# 4xthermocoupleshield.net
KiCad netlist of a schematic drawn in EAGLE
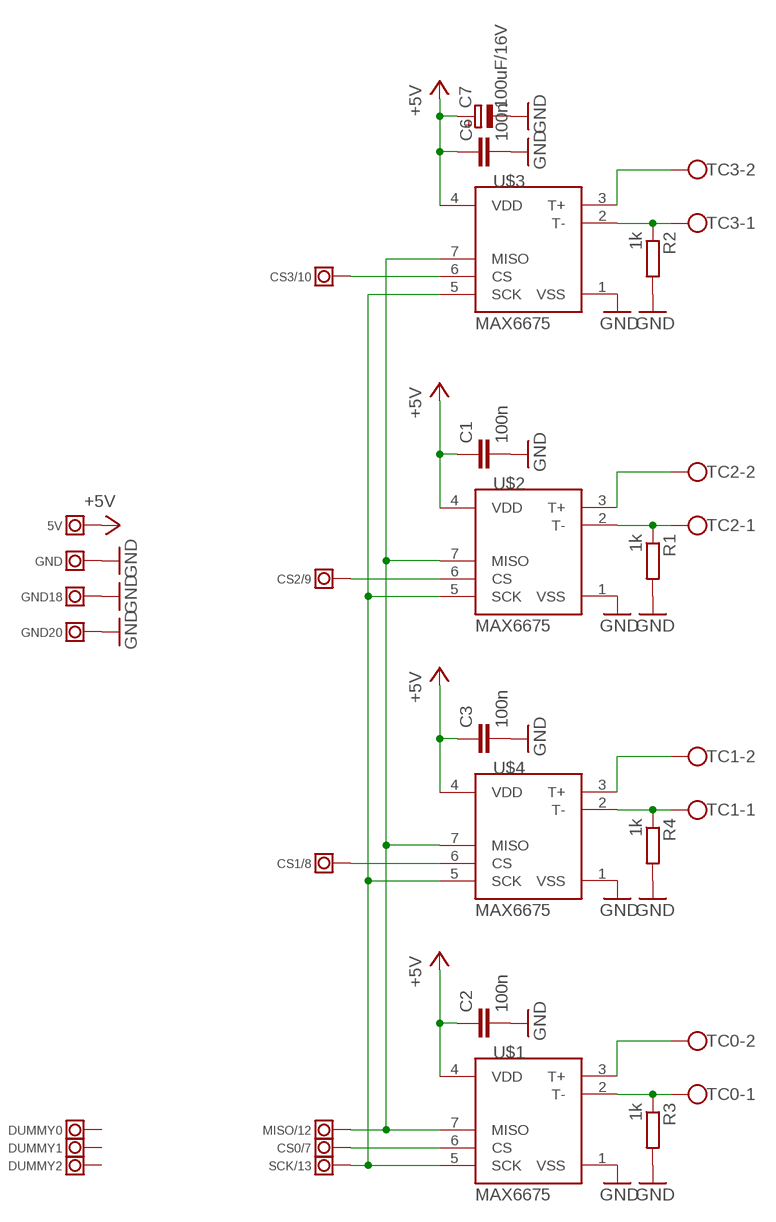
[diagram p0: schematic, sheet 1]

(export (version "E")
  (design (tool "Eeschema 10.0.6"))
  (components
    (comp (ref "5V")
      (value "PIN-HEADER")
      (footprint "eagle-import:PIN-HEADER-MALE")
      (libsource (lib "eagle-import") (part "PIN-HEADER"))
    )
    (comp (ref "C1")
      (value "100n")
      (footprint "eagle-import:C0603")
      (libsource (lib "eagle-import") (part "C-EUC0603"))
    )
    (comp (ref "C2")
      (value "100n")
      (footprint "eagle-import:C0603")
      (libsource (lib "eagle-import") (part "C-EUC0603"))
    )
    (comp (ref "C3")
      (value "100n")
      (footprint "eagle-import:C0603")
      (libsource (lib "eagle-import") (part "C-EUC0603"))
    )
    (comp (ref "C6")
      (value "100n")
      (footprint "eagle-import:C0603")
      (libsource (lib "eagle-import") (part "C-EUC0603"))
    )
    (comp (ref "C7")
      (value "100uF/16V")
      (footprint "eagle-import:E2,5-7")
      (libsource (lib "eagle-import") (part "CPOL-EUE2.5-7"))
    )
    (comp (ref "CS0/7")
      (value "PIN-HEADER")
      (footprint "eagle-import:PIN-HEADER-MALE")
      (libsource (lib "eagle-import") (part "PIN-HEADER"))
    )
    (comp (ref "CS1/8")
      (value "PIN-HEADER")
      (footprint "eagle-import:PIN-HEADER-MALE")
      (libsource (lib "eagle-import") (part "PIN-HEADER"))
    )
    (comp (ref "CS2/9")
      (value "PIN-HEADER")
      (footprint "eagle-import:PIN-HEADER-MALE")
      (libsource (lib "eagle-import") (part "PIN-HEADER"))
    )
    (comp (ref "CS3/10")
      (value "PIN-HEADER")
      (footprint "eagle-import:PIN-HEADER-MALE")
      (libsource (lib "eagle-import") (part "PIN-HEADER"))
    )
    (comp (ref "DUMMY0")
      (value "PIN-HEADER")
      (footprint "eagle-import:PIN-HEADER-MALE")
      (libsource (lib "eagle-import") (part "PIN-HEADER"))
    )
    (comp (ref "DUMMY1")
      (value "PIN-HEADER")
      (footprint "eagle-import:PIN-HEADER-MALE")
      (libsource (lib "eagle-import") (part "PIN-HEADER"))
    )
    (comp (ref "DUMMY2")
      (value "PIN-HEADER")
      (footprint "eagle-import:PIN-HEADER-MALE")
      (libsource (lib "eagle-import") (part "PIN-HEADER"))
    )
    (comp (ref "GND")
      (value "PIN-HEADER")
      (footprint "eagle-import:PIN-HEADER-MALE")
      (libsource (lib "eagle-import") (part "PIN-HEADER"))
    )
    (comp (ref "GND18")
      (value "PIN-HEADER")
      (footprint "eagle-import:PIN-HEADER-MALE")
      (libsource (lib "eagle-import") (part "PIN-HEADER"))
    )
    (comp (ref "GND20")
      (value "PIN-HEADER")
      (footprint "eagle-import:PIN-HEADER-MALE")
      (libsource (lib "eagle-import") (part "PIN-HEADER"))
    )
    (comp (ref "MISO/12")
      (value "PIN-HEADER")
      (footprint "eagle-import:PIN-HEADER-MALE")
      (libsource (lib "eagle-import") (part "PIN-HEADER"))
    )
    (comp (ref "R1")
      (value "1k")
      (footprint "eagle-import:R0603")
      (libsource (lib "eagle-import") (part "R-EU_R0603"))
    )
    (comp (ref "R2")
      (value "1k")
      (footprint "eagle-import:R0603")
      (libsource (lib "eagle-import") (part "R-EU_R0603"))
    )
    (comp (ref "R3")
      (value "1k")
      (footprint "eagle-import:R0603")
      (libsource (lib "eagle-import") (part "R-EU_R0603"))
    )
    (comp (ref "R4")
      (value "1k")
      (footprint "eagle-import:R0603")
      (libsource (lib "eagle-import") (part "R-EU_R0603"))
    )
    (comp (ref "SCK/13")
      (value "PIN-HEADER")
      (footprint "eagle-import:PIN-HEADER-MALE")
      (libsource (lib "eagle-import") (part "PIN-HEADER"))
    )
    (comp (ref "TC0")
      (value "W237-102")
      (footprint "eagle-import:W237-102")
      (libsource (lib "eagle-import") (part "W237-102"))
    )
    (comp (ref "TC1")
      (value "W237-102")
      (footprint "eagle-import:W237-102")
      (libsource (lib "eagle-import") (part "W237-102"))
    )
    (comp (ref "TC2")
      (value "W237-102")
      (footprint "eagle-import:W237-102")
      (libsource (lib "eagle-import") (part "W237-102"))
    )
    (comp (ref "TC3")
      (value "W237-102")
      (footprint "eagle-import:W237-102")
      (libsource (lib "eagle-import") (part "W237-102"))
    )
    (comp (ref "U$1")
      (value "MAX6675")
      (footprint "eagle-import:SO08-MAX6675")
      (libsource (lib "eagle-import") (part "MAX6675"))
    )
    (comp (ref "U$2")
      (value "MAX6675")
      (footprint "eagle-import:SO08-MAX6675")
      (libsource (lib "eagle-import") (part "MAX6675"))
    )
    (comp (ref "U$3")
      (value "MAX6675")
      (footprint "eagle-import:SO08-MAX6675")
      (libsource (lib "eagle-import") (part "MAX6675"))
    )
    (comp (ref "U$4")
      (value "MAX6675")
      (footprint "eagle-import:SO08-MAX6675")
      (libsource (lib "eagle-import") (part "MAX6675"))
    )
  )
  (nets
    (net (code "1") (name "+5V") (class "Default")
      (node (ref "5V") (pin "P$1") (pinfunction "P$1_P$1") (pintype "bidirectional"))
      (node (ref "C1") (pin "1") (pinfunction "1_1") (pintype "passive"))
      (node (ref "C2") (pin "1") (pinfunction "1_1") (pintype "passive"))
      (node (ref "C3") (pin "1") (pinfunction "1_1") (pintype "passive"))
      (node (ref "C6") (pin "1") (pinfunction "1_1") (pintype "passive"))
      (node (ref "C7") (pin "+") (pinfunction "+_+") (pintype "passive"))
      (node (ref "U$1") (pin "4") (pinfunction "VDD_4") (pintype "bidirectional"))
      (node (ref "U$2") (pin "4") (pinfunction "VDD_4") (pintype "bidirectional"))
      (node (ref "U$3") (pin "4") (pinfunction "VDD_4") (pintype "bidirectional"))
      (node (ref "U$4") (pin "4") (pinfunction "VDD_4") (pintype "bidirectional"))
    )
    (net (code "2") (name "GND") (class "Default")
      (node (ref "C1") (pin "2") (pinfunction "2_2") (pintype "passive"))
      (node (ref "C2") (pin "2") (pinfunction "2_2") (pintype "passive"))
      (node (ref "C3") (pin "2") (pinfunction "2_2") (pintype "passive"))
      (node (ref "C6") (pin "2") (pinfunction "2_2") (pintype "passive"))
      (node (ref "C7") (pin "-") (pinfunction "-_-") (pintype "passive"))
      (node (ref "GND") (pin "P$1") (pinfunction "P$1_P$1") (pintype "bidirectional"))
      (node (ref "GND18") (pin "P$1") (pinfunction "P$1_P$1") (pintype "bidirectional"))
      (node (ref "GND20") (pin "P$1") (pinfunction "P$1_P$1") (pintype "bidirectional"))
      (node (ref "R1") (pin "2") (pinfunction "2_2") (pintype "passive"))
      (node (ref "R2") (pin "2") (pinfunction "2_2") (pintype "passive"))
      (node (ref "R3") (pin "2") (pinfunction "2_2") (pintype "passive"))
      (node (ref "R4") (pin "2") (pinfunction "2_2") (pintype "passive"))
      (node (ref "U$1") (pin "1") (pinfunction "VSS_1") (pintype "bidirectional"))
      (node (ref "U$2") (pin "1") (pinfunction "VSS_1") (pintype "bidirectional"))
      (node (ref "U$3") (pin "1") (pinfunction "VSS_1") (pintype "bidirectional"))
      (node (ref "U$4") (pin "1") (pinfunction "VSS_1") (pintype "bidirectional"))
    )
    (net (code "3") (name "Net-(TC0A-KL)") (class "Default")
      (node (ref "R3") (pin "1") (pinfunction "1_1") (pintype "passive"))
      (node (ref "TC0") (pin "1") (pinfunction "KL_1") (pintype "passive"))
      (node (ref "U$1") (pin "2") (pinfunction "T-_2") (pintype "bidirectional"))
    )
    (net (code "4") (name "Net-(TC0B-KL)") (class "Default")
      (node (ref "TC0") (pin "2") (pinfunction "KL_2") (pintype "passive"))
      (node (ref "U$1") (pin "3") (pinfunction "T+_3") (pintype "bidirectional"))
    )
    (net (code "5") (name "Net-(TC1A-KL)") (class "Default")
      (node (ref "R4") (pin "1") (pinfunction "1_1") (pintype "passive"))
      (node (ref "TC1") (pin "1") (pinfunction "KL_1") (pintype "passive"))
      (node (ref "U$4") (pin "2") (pinfunction "T-_2") (pintype "bidirectional"))
    )
    (net (code "6") (name "Net-(TC1B-KL)") (class "Default")
      (node (ref "TC1") (pin "2") (pinfunction "KL_2") (pintype "passive"))
      (node (ref "U$4") (pin "3") (pinfunction "T+_3") (pintype "bidirectional"))
    )
    (net (code "7") (name "Net-(TC2A-KL)") (class "Default")
      (node (ref "R1") (pin "1") (pinfunction "1_1") (pintype "passive"))
      (node (ref "TC2") (pin "1") (pinfunction "KL_1") (pintype "passive"))
      (node (ref "U$2") (pin "2") (pinfunction "T-_2") (pintype "bidirectional"))
    )
    (net (code "8") (name "Net-(TC2B-KL)") (class "Default")
      (node (ref "TC2") (pin "2") (pinfunction "KL_2") (pintype "passive"))
      (node (ref "U$2") (pin "3") (pinfunction "T+_3") (pintype "bidirectional"))
    )
    (net (code "9") (name "Net-(TC3A-KL)") (class "Default")
      (node (ref "R2") (pin "1") (pinfunction "1_1") (pintype "passive"))
      (node (ref "TC3") (pin "1") (pinfunction "KL_1") (pintype "passive"))
      (node (ref "U$3") (pin "2") (pinfunction "T-_2") (pintype "bidirectional"))
    )
    (net (code "10") (name "Net-(TC3B-KL)") (class "Default")
      (node (ref "TC3") (pin "2") (pinfunction "KL_2") (pintype "passive"))
      (node (ref "U$3") (pin "3") (pinfunction "T+_3") (pintype "bidirectional"))
    )
    (net (code "11") (name "Net-(U$1-CS)") (class "Default")
      (node (ref "CS0/7") (pin "P$1") (pinfunction "P$1_P$1") (pintype "bidirectional"))
      (node (ref "U$1") (pin "6") (pinfunction "CS_6") (pintype "bidirectional"))
    )
    (net (code "12") (name "Net-(U$1-MISO)") (class "Default")
      (node (ref "MISO/12") (pin "P$1") (pinfunction "P$1_P$1") (pintype "bidirectional"))
      (node (ref "U$1") (pin "7") (pinfunction "MISO_7") (pintype "bidirectional"))
      (node (ref "U$2") (pin "7") (pinfunction "MISO_7") (pintype "bidirectional"))
      (node (ref "U$3") (pin "7") (pinfunction "MISO_7") (pintype "bidirectional"))
      (node (ref "U$4") (pin "7") (pinfunction "MISO_7") (pintype "bidirectional"))
    )
    (net (code "13") (name "Net-(U$1-SCK)") (class "Default")
      (node (ref "SCK/13") (pin "P$1") (pinfunction "P$1_P$1") (pintype "bidirectional"))
      (node (ref "U$1") (pin "5") (pinfunction "SCK_5") (pintype "bidirectional"))
      (node (ref "U$2") (pin "5") (pinfunction "SCK_5") (pintype "bidirectional"))
      (node (ref "U$3") (pin "5") (pinfunction "SCK_5") (pintype "bidirectional"))
      (node (ref "U$4") (pin "5") (pinfunction "SCK_5") (pintype "bidirectional"))
    )
    (net (code "14") (name "Net-(U$2-CS)") (class "Default")
      (node (ref "CS2/9") (pin "P$1") (pinfunction "P$1_P$1") (pintype "bidirectional"))
      (node (ref "U$2") (pin "6") (pinfunction "CS_6") (pintype "bidirectional"))
    )
    (net (code "15") (name "Net-(U$3-CS)") (class "Default")
      (node (ref "CS3/10") (pin "P$1") (pinfunction "P$1_P$1") (pintype "bidirectional"))
      (node (ref "U$3") (pin "6") (pinfunction "CS_6") (pintype "bidirectional"))
    )
    (net (code "16") (name "Net-(U$4-CS)") (class "Default")
      (node (ref "CS1/8") (pin "P$1") (pinfunction "P$1_P$1") (pintype "bidirectional"))
      (node (ref "U$4") (pin "6") (pinfunction "CS_6") (pintype "bidirectional"))
    )
    (net (code "17") (name "unconnected-(DUMMY0-PadP$1)") (class "Default")
      (node (ref "DUMMY0") (pin "P$1") (pinfunction "P$1_P$1") (pintype "bidirectional"))
    )
    (net (code "18") (name "unconnected-(DUMMY1-PadP$1)") (class "Default")
      (node (ref "DUMMY1") (pin "P$1") (pinfunction "P$1_P$1") (pintype "bidirectional"))
    )
    (net (code "19") (name "unconnected-(DUMMY2-PadP$1)") (class "Default")
      (node (ref "DUMMY2") (pin "P$1") (pinfunction "P$1_P$1") (pintype "bidirectional"))
    )
  )
)
